# Displaying_Unit.net
KiCad netlist of a schematic drawn in Altium Designer
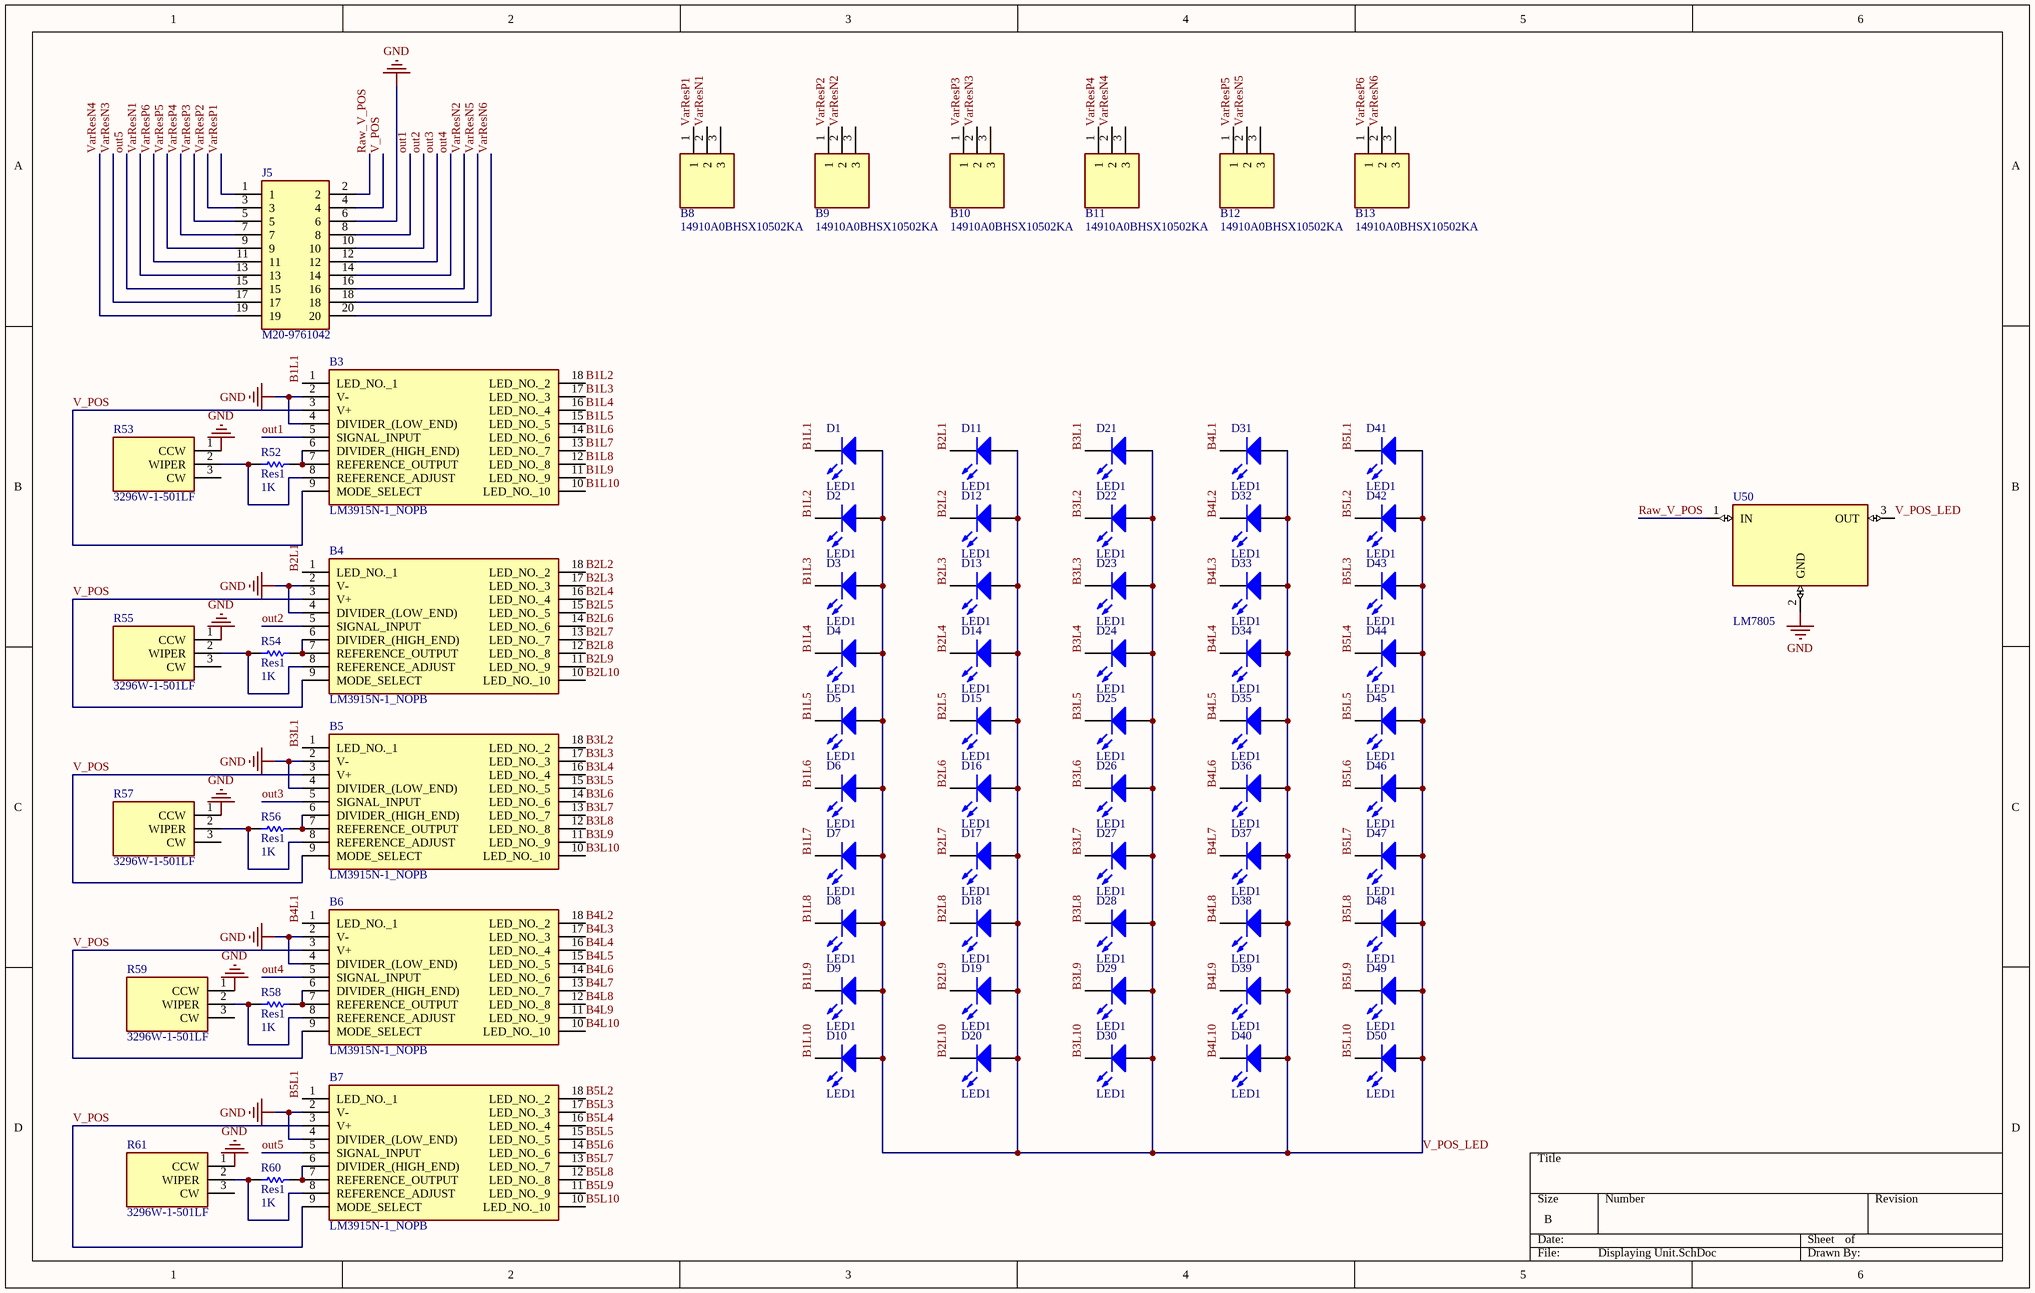
[diagram p0: Displaying Unit.SchDoc]

(export (version "E")
  (design (tool "Eeschema 10.0.6"))
  (components
    (comp (ref "B3")
      (value "LM3915N-1_NOPB")
      (footprint "DIP794W56P254L2286H533Q18N")
      (fields
        (field (name "MANUFACTURER_PART_NUMBER") "LM3915N-1/NOPB")
        (field (name "MOUSER PART NUMBER") "926-LM3915N-1/NOPB")
      )
      (libsource (lib "LM3915N-1_NOPB") (part "LM3915N-1_NOPB"))
    )
    (comp (ref "B4")
      (value "LM3915N-1_NOPB")
      (footprint "DIP794W56P254L2286H533Q18N")
      (fields
        (field (name "MANUFACTURER_PART_NUMBER") "LM3915N-1/NOPB")
        (field (name "MOUSER PART NUMBER") "926-LM3915N-1/NOPB")
      )
      (libsource (lib "LM3915N-1_NOPB") (part "LM3915N-1_NOPB"))
    )
    (comp (ref "B5")
      (value "LM3915N-1_NOPB")
      (footprint "DIP794W56P254L2286H533Q18N")
      (fields
        (field (name "MANUFACTURER_PART_NUMBER") "LM3915N-1/NOPB")
        (field (name "MOUSER PART NUMBER") "926-LM3915N-1/NOPB")
      )
      (libsource (lib "LM3915N-1_NOPB") (part "LM3915N-1_NOPB"))
    )
    (comp (ref "B6")
      (value "LM3915N-1_NOPB")
      (footprint "DIP794W56P254L2286H533Q18N")
      (fields
        (field (name "MANUFACTURER_PART_NUMBER") "LM3915N-1/NOPB")
        (field (name "MOUSER PART NUMBER") "926-LM3915N-1/NOPB")
      )
      (libsource (lib "LM3915N-1_NOPB") (part "LM3915N-1_NOPB"))
    )
    (comp (ref "B7")
      (value "LM3915N-1_NOPB")
      (footprint "DIP794W56P254L2286H533Q18N")
      (fields
        (field (name "MANUFACTURER_PART_NUMBER") "LM3915N-1/NOPB")
        (field (name "MOUSER PART NUMBER") "926-LM3915N-1/NOPB")
      )
      (libsource (lib "LM3915N-1_NOPB") (part "LM3915N-1_NOPB"))
    )
    (comp (ref "B8")
      (value "14910A0BHSX10502KA")
      (footprint "14910F0GJSX10103KA")
      (description "Potentiometers 1/2' SQ 1/4'S 5Kohms Cermet")
      (fields (field (name "MOUSER PART NUMBER") "594-14910A0BHSP502KA"))
      (libsource (lib "14910A0BHSX10502KA") (part "14910A0BHSX10502KA"))
    )
    (comp (ref "B9")
      (value "14910A0BHSX10502KA")
      (footprint "14910F0GJSX10103KA")
      (description "Potentiometers 1/2' SQ 1/4'S 5Kohms Cermet")
      (fields (field (name "MOUSER PART NUMBER") "594-14910A0BHSP502KA"))
      (libsource (lib "14910A0BHSX10502KA") (part "14910A0BHSX10502KA"))
    )
    (comp (ref "B10")
      (value "14910A0BHSX10502KA")
      (footprint "14910F0GJSX10103KA")
      (description "Potentiometers 1/2' SQ 1/4'S 5Kohms Cermet")
      (fields (field (name "MOUSER PART NUMBER") "594-14910A0BHSP502KA"))
      (libsource (lib "14910A0BHSX10502KA") (part "14910A0BHSX10502KA"))
    )
    (comp (ref "B11")
      (value "14910A0BHSX10502KA")
      (footprint "14910F0GJSX10103KA")
      (description "Potentiometers 1/2' SQ 1/4'S 5Kohms Cermet")
      (fields (field (name "MOUSER PART NUMBER") "594-14910A0BHSP502KA"))
      (libsource (lib "14910A0BHSX10502KA") (part "14910A0BHSX10502KA"))
    )
    (comp (ref "B12")
      (value "14910A0BHSX10502KA")
      (footprint "14910F0GJSX10103KA")
      (description "Potentiometers 1/2' SQ 1/4'S 5Kohms Cermet")
      (fields (field (name "MOUSER PART NUMBER") "594-14910A0BHSP502KA"))
      (libsource (lib "14910A0BHSX10502KA") (part "14910A0BHSX10502KA"))
    )
    (comp (ref "B13")
      (value "14910A0BHSX10502KA")
      (footprint "14910F0GJSX10103KA")
      (description "Potentiometers 1/2' SQ 1/4'S 5Kohms Cermet")
      (fields (field (name "MOUSER PART NUMBER") "594-14910A0BHSP502KA"))
      (libsource (lib "14910A0BHSX10502KA") (part "14910A0BHSX10502KA"))
    )
    (comp (ref "D1")
      (value "LED1")
      (footprint "LED-1")
      (description "Typical RED GaAs LED")
      (fields (field (name "PUBLISHER") "Altium Limited"))
      (libsource (lib "Miscellaneous Devices") (part "LED1"))
    )
    (comp (ref "D2")
      (value "LED1")
      (footprint "LED-1")
      (description "Typical RED GaAs LED")
      (fields (field (name "PUBLISHER") "Altium Limited"))
      (libsource (lib "Miscellaneous Devices") (part "LED1"))
    )
    (comp (ref "D3")
      (value "LED1")
      (footprint "LED-1")
      (description "Typical RED GaAs LED")
      (fields (field (name "PUBLISHER") "Altium Limited"))
      (libsource (lib "Miscellaneous Devices") (part "LED1"))
    )
    (comp (ref "D4")
      (value "LED1")
      (footprint "LED-1")
      (description "Typical RED GaAs LED")
      (fields (field (name "PUBLISHER") "Altium Limited"))
      (libsource (lib "Miscellaneous Devices") (part "LED1"))
    )
    (comp (ref "D5")
      (value "LED1")
      (footprint "LED-1")
      (description "Typical RED GaAs LED")
      (fields (field (name "PUBLISHER") "Altium Limited"))
      (libsource (lib "Miscellaneous Devices") (part "LED1"))
    )
    (comp (ref "D6")
      (value "LED1")
      (footprint "LED-1")
      (description "Typical RED GaAs LED")
      (fields (field (name "PUBLISHER") "Altium Limited"))
      (libsource (lib "Miscellaneous Devices") (part "LED1"))
    )
    (comp (ref "D7")
      (value "LED1")
      (footprint "LED-1")
      (description "Typical RED GaAs LED")
      (fields (field (name "PUBLISHER") "Altium Limited"))
      (libsource (lib "Miscellaneous Devices") (part "LED1"))
    )
    (comp (ref "D8")
      (value "LED1")
      (footprint "LED-1")
      (description "Typical RED GaAs LED")
      (fields (field (name "PUBLISHER") "Altium Limited"))
      (libsource (lib "Miscellaneous Devices") (part "LED1"))
    )
    (comp (ref "D9")
      (value "LED1")
      (footprint "LED-1")
      (description "Typical RED GaAs LED")
      (fields (field (name "PUBLISHER") "Altium Limited"))
      (libsource (lib "Miscellaneous Devices") (part "LED1"))
    )
    (comp (ref "D10")
      (value "LED1")
      (footprint "LED-1")
      (description "Typical RED GaAs LED")
      (fields (field (name "PUBLISHER") "Altium Limited"))
      (libsource (lib "Miscellaneous Devices") (part "LED1"))
    )
    (comp (ref "D11")
      (value "LED1")
      (footprint "LED-1")
      (description "Typical RED GaAs LED")
      (fields (field (name "PUBLISHER") "Altium Limited"))
      (libsource (lib "Miscellaneous Devices") (part "LED1"))
    )
    (comp (ref "D12")
      (value "LED1")
      (footprint "LED-1")
      (description "Typical RED GaAs LED")
      (fields (field (name "PUBLISHER") "Altium Limited"))
      (libsource (lib "Miscellaneous Devices") (part "LED1"))
    )
    (comp (ref "D13")
      (value "LED1")
      (footprint "LED-1")
      (description "Typical RED GaAs LED")
      (fields (field (name "PUBLISHER") "Altium Limited"))
      (libsource (lib "Miscellaneous Devices") (part "LED1"))
    )
    (comp (ref "D14")
      (value "LED1")
      (footprint "LED-1")
      (description "Typical RED GaAs LED")
      (fields (field (name "PUBLISHER") "Altium Limited"))
      (libsource (lib "Miscellaneous Devices") (part "LED1"))
    )
    (comp (ref "D15")
      (value "LED1")
      (footprint "LED-1")
      (description "Typical RED GaAs LED")
      (fields (field (name "PUBLISHER") "Altium Limited"))
      (libsource (lib "Miscellaneous Devices") (part "LED1"))
    )
    (comp (ref "D16")
      (value "LED1")
      (footprint "LED-1")
      (description "Typical RED GaAs LED")
      (fields (field (name "PUBLISHER") "Altium Limited"))
      (libsource (lib "Miscellaneous Devices") (part "LED1"))
    )
    (comp (ref "D17")
      (value "LED1")
      (footprint "LED-1")
      (description "Typical RED GaAs LED")
      (fields (field (name "PUBLISHER") "Altium Limited"))
      (libsource (lib "Miscellaneous Devices") (part "LED1"))
    )
    (comp (ref "D18")
      (value "LED1")
      (footprint "LED-1")
      (description "Typical RED GaAs LED")
      (fields (field (name "PUBLISHER") "Altium Limited"))
      (libsource (lib "Miscellaneous Devices") (part "LED1"))
    )
    (comp (ref "D19")
      (value "LED1")
      (footprint "LED-1")
      (description "Typical RED GaAs LED")
      (fields (field (name "PUBLISHER") "Altium Limited"))
      (libsource (lib "Miscellaneous Devices") (part "LED1"))
    )
    (comp (ref "D20")
      (value "LED1")
      (footprint "LED-1")
      (description "Typical RED GaAs LED")
      (fields (field (name "PUBLISHER") "Altium Limited"))
      (libsource (lib "Miscellaneous Devices") (part "LED1"))
    )
    (comp (ref "D21")
      (value "LED1")
      (footprint "LED-1")
      (description "Typical RED GaAs LED")
      (fields (field (name "PUBLISHER") "Altium Limited"))
      (libsource (lib "Miscellaneous Devices") (part "LED1"))
    )
    (comp (ref "D22")
      (value "LED1")
      (footprint "LED-1")
      (description "Typical RED GaAs LED")
      (fields (field (name "PUBLISHER") "Altium Limited"))
      (libsource (lib "Miscellaneous Devices") (part "LED1"))
    )
    (comp (ref "D23")
      (value "LED1")
      (footprint "LED-1")
      (description "Typical RED GaAs LED")
      (fields (field (name "PUBLISHER") "Altium Limited"))
      (libsource (lib "Miscellaneous Devices") (part "LED1"))
    )
    (comp (ref "D24")
      (value "LED1")
      (footprint "LED-1")
      (description "Typical RED GaAs LED")
      (fields (field (name "PUBLISHER") "Altium Limited"))
      (libsource (lib "Miscellaneous Devices") (part "LED1"))
    )
    (comp (ref "D25")
      (value "LED1")
      (footprint "LED-1")
      (description "Typical RED GaAs LED")
      (fields (field (name "PUBLISHER") "Altium Limited"))
      (libsource (lib "Miscellaneous Devices") (part "LED1"))
    )
    (comp (ref "D26")
      (value "LED1")
      (footprint "LED-1")
      (description "Typical RED GaAs LED")
      (fields (field (name "PUBLISHER") "Altium Limited"))
      (libsource (lib "Miscellaneous Devices") (part "LED1"))
    )
    (comp (ref "D27")
      (value "LED1")
      (footprint "LED-1")
      (description "Typical RED GaAs LED")
      (fields (field (name "PUBLISHER") "Altium Limited"))
      (libsource (lib "Miscellaneous Devices") (part "LED1"))
    )
    (comp (ref "D28")
      (value "LED1")
      (footprint "LED-1")
      (description "Typical RED GaAs LED")
      (fields (field (name "PUBLISHER") "Altium Limited"))
      (libsource (lib "Miscellaneous Devices") (part "LED1"))
    )
    (comp (ref "D29")
      (value "LED1")
      (footprint "LED-1")
      (description "Typical RED GaAs LED")
      (fields (field (name "PUBLISHER") "Altium Limited"))
      (libsource (lib "Miscellaneous Devices") (part "LED1"))
    )
    (comp (ref "D30")
      (value "LED1")
      (footprint "LED-1")
      (description "Typical RED GaAs LED")
      (fields (field (name "PUBLISHER") "Altium Limited"))
      (libsource (lib "Miscellaneous Devices") (part "LED1"))
    )
    (comp (ref "D31")
      (value "LED1")
      (footprint "LED-1")
      (description "Typical RED GaAs LED")
      (fields (field (name "PUBLISHER") "Altium Limited"))
      (libsource (lib "Miscellaneous Devices") (part "LED1"))
    )
    (comp (ref "D32")
      (value "LED1")
      (footprint "LED-1")
      (description "Typical RED GaAs LED")
      (fields (field (name "PUBLISHER") "Altium Limited"))
      (libsource (lib "Miscellaneous Devices") (part "LED1"))
    )
    (comp (ref "D33")
      (value "LED1")
      (footprint "LED-1")
      (description "Typical RED GaAs LED")
      (fields (field (name "PUBLISHER") "Altium Limited"))
      (libsource (lib "Miscellaneous Devices") (part "LED1"))
    )
    (comp (ref "D34")
      (value "LED1")
      (footprint "LED-1")
      (description "Typical RED GaAs LED")
      (fields (field (name "PUBLISHER") "Altium Limited"))
      (libsource (lib "Miscellaneous Devices") (part "LED1"))
    )
    (comp (ref "D35")
      (value "LED1")
      (footprint "LED-1")
      (description "Typical RED GaAs LED")
      (fields (field (name "PUBLISHER") "Altium Limited"))
      (libsource (lib "Miscellaneous Devices") (part "LED1"))
    )
    (comp (ref "D36")
      (value "LED1")
      (footprint "LED-1")
      (description "Typical RED GaAs LED")
      (fields (field (name "PUBLISHER") "Altium Limited"))
      (libsource (lib "Miscellaneous Devices") (part "LED1"))
    )
    (comp (ref "D37")
      (value "LED1")
      (footprint "LED-1")
      (description "Typical RED GaAs LED")
      (fields (field (name "PUBLISHER") "Altium Limited"))
      (libsource (lib "Miscellaneous Devices") (part "LED1"))
    )
    (comp (ref "D38")
      (value "LED1")
      (footprint "LED-1")
      (description "Typical RED GaAs LED")
      (fields (field (name "PUBLISHER") "Altium Limited"))
      (libsource (lib "Miscellaneous Devices") (part "LED1"))
    )
    (comp (ref "D39")
      (value "LED1")
      (footprint "LED-1")
      (description "Typical RED GaAs LED")
      (fields (field (name "PUBLISHER") "Altium Limited"))
      (libsource (lib "Miscellaneous Devices") (part "LED1"))
    )
    (comp (ref "D40")
      (value "LED1")
      (footprint "LED-1")
      (description "Typical RED GaAs LED")
      (fields (field (name "PUBLISHER") "Altium Limited"))
      (libsource (lib "Miscellaneous Devices") (part "LED1"))
    )
    (comp (ref "D41")
      (value "LED1")
      (footprint "LED-1")
      (description "Typical RED GaAs LED")
      (fields (field (name "PUBLISHER") "Altium Limited"))
      (libsource (lib "Miscellaneous Devices") (part "LED1"))
    )
    (comp (ref "D42")
      (value "LED1")
      (footprint "LED-1")
      (description "Typical RED GaAs LED")
      (fields (field (name "PUBLISHER") "Altium Limited"))
      (libsource (lib "Miscellaneous Devices") (part "LED1"))
    )
    (comp (ref "D43")
      (value "LED1")
      (footprint "LED-1")
      (description "Typical RED GaAs LED")
      (fields (field (name "PUBLISHER") "Altium Limited"))
      (libsource (lib "Miscellaneous Devices") (part "LED1"))
    )
    (comp (ref "D44")
      (value "LED1")
      (footprint "LED-1")
      (description "Typical RED GaAs LED")
      (fields (field (name "PUBLISHER") "Altium Limited"))
      (libsource (lib "Miscellaneous Devices") (part "LED1"))
    )
    (comp (ref "D45")
      (value "LED1")
      (footprint "LED-1")
      (description "Typical RED GaAs LED")
      (fields (field (name "PUBLISHER") "Altium Limited"))
      (libsource (lib "Miscellaneous Devices") (part "LED1"))
    )
    (comp (ref "D46")
      (value "LED1")
      (footprint "LED-1")
      (description "Typical RED GaAs LED")
      (fields (field (name "PUBLISHER") "Altium Limited"))
      (libsource (lib "Miscellaneous Devices") (part "LED1"))
    )
    (comp (ref "D47")
      (value "LED1")
      (footprint "LED-1")
      (description "Typical RED GaAs LED")
      (fields (field (name "PUBLISHER") "Altium Limited"))
      (libsource (lib "Miscellaneous Devices") (part "LED1"))
    )
    (comp (ref "D48")
      (value "LED1")
      (footprint "LED-1")
      (description "Typical RED GaAs LED")
      (fields (field (name "PUBLISHER") "Altium Limited"))
      (libsource (lib "Miscellaneous Devices") (part "LED1"))
    )
    (comp (ref "D49")
      (value "LED1")
      (footprint "LED-1")
      (description "Typical RED GaAs LED")
      (fields (field (name "PUBLISHER") "Altium Limited"))
      (libsource (lib "Miscellaneous Devices") (part "LED1"))
    )
    (comp (ref "D50")
      (value "LED1")
      (footprint "LED-1")
      (description "Typical RED GaAs LED")
      (fields (field (name "PUBLISHER") "Altium Limited"))
      (libsource (lib "Miscellaneous Devices") (part "LED1"))
    )
    (comp (ref "J5")
      (value "M20-9761042")
      (footprint "HDRV20W64P254_2X10_2540X508X838P")
      (description "Headers & Wire Housings 10+10 DIL VERTICAL PIN HEADER GOLD+TIN")
      (fields (field (name "MOUSER PART NUMBER") "855-M20-9761042"))
      (libsource (lib "M20-9761042") (part "M20-9761042"))
    )
    (comp (ref "R52")
      (value "Res1")
      (footprint "AXIAL-0.3")
      (description "Resistor")
      (fields (field (name "ALTIUM_VALUE") "1K") (field (name "PUBLISHER") "Altium Limited"))
      (libsource (lib "Miscellaneous Devices") (part "Res1"))
    )
    (comp (ref "R53")
      (value "3296W-1-501LF")
      (footprint "3296W1501LF")
      (description "Trimmer Resistors - Through Hole 3/8IN 500 OHM Sealed Vertical Adjust")
      (fields (field (name "MOUSER PART NUMBER") "652-3296W-1-501LF"))
      (libsource (lib "3296W-1-501LF") (part "3296W-1-501LF"))
    )
    (comp (ref "R54")
      (value "Res1")
      (footprint "AXIAL-0.3")
      (description "Resistor")
      (fields (field (name "ALTIUM_VALUE") "1K") (field (name "PUBLISHER") "Altium Limited"))
      (libsource (lib "Miscellaneous Devices") (part "Res1"))
    )
    (comp (ref "R55")
      (value "3296W-1-501LF")
      (footprint "3296W1501LF")
      (description "Trimmer Resistors - Through Hole 3/8IN 500 OHM Sealed Vertical Adjust")
      (fields (field (name "MOUSER PART NUMBER") "652-3296W-1-501LF"))
      (libsource (lib "3296W-1-501LF") (part "3296W-1-501LF"))
    )
    (comp (ref "R56")
      (value "Res1")
      (footprint "AXIAL-0.3")
      (description "Resistor")
      (fields (field (name "ALTIUM_VALUE") "1K") (field (name "PUBLISHER") "Altium Limited"))
      (libsource (lib "Miscellaneous Devices") (part "Res1"))
    )
    (comp (ref "R57")
      (value "3296W-1-501LF")
      (footprint "3296W1501LF")
      (description "Trimmer Resistors - Through Hole 3/8IN 500 OHM Sealed Vertical Adjust")
      (fields (field (name "MOUSER PART NUMBER") "652-3296W-1-501LF"))
      (libsource (lib "3296W-1-501LF") (part "3296W-1-501LF"))
    )
    (comp (ref "R58")
      (value "Res1")
      (footprint "AXIAL-0.3")
      (description "Resistor")
      (fields (field (name "ALTIUM_VALUE") "1K") (field (name "PUBLISHER") "Altium Limited"))
      (libsource (lib "Miscellaneous Devices") (part "Res1"))
    )
    (comp (ref "R59")
      (value "3296W-1-501LF")
      (footprint "3296W1501LF")
      (description "Trimmer Resistors - Through Hole 3/8IN 500 OHM Sealed Vertical Adjust")
      (fields (field (name "MOUSER PART NUMBER") "652-3296W-1-501LF"))
      (libsource (lib "3296W-1-501LF") (part "3296W-1-501LF"))
    )
    (comp (ref "R60")
      (value "Res1")
      (footprint "AXIAL-0.3")
      (description "Resistor")
      (fields (field (name "ALTIUM_VALUE") "1K") (field (name "PUBLISHER") "Altium Limited"))
      (libsource (lib "Miscellaneous Devices") (part "Res1"))
    )
    (comp (ref "R61")
      (value "3296W-1-501LF")
      (footprint "3296W1501LF")
      (description "Trimmer Resistors - Through Hole 3/8IN 500 OHM Sealed Vertical Adjust")
      (fields (field (name "MOUSER PART NUMBER") "652-3296W-1-501LF"))
      (libsource (lib "3296W-1-501LF") (part "3296W-1-501LF"))
    )
    (comp (ref "U50")
      (value "LM7805")
      (footprint "TO220")
      (description "Linear Voltage Regulator IC Positive Fixed 1 Output 1.5A DDPAK/TO-263-3")
      (fields (field (name "MF") "Texas Instruments"))
      (libsource (lib "LM7805") (part "LM7805"))
    )
  )
  (nets
    (net (code "1") (name "/B1L1") (class "Default")
      (node (ref "B3") (pin "1") (pinfunction "LED_NO._1_1") (pintype "passive"))
      (node (ref "D1") (pin "2") (pinfunction "K_2") (pintype "passive"))
    )
    (net (code "2") (name "/B1L2") (class "Default")
      (node (ref "B3") (pin "18") (pinfunction "LED_NO._2_18") (pintype "passive"))
      (node (ref "D2") (pin "2") (pinfunction "K_2") (pintype "passive"))
    )
    (net (code "3") (name "/B1L3") (class "Default")
      (node (ref "B3") (pin "17") (pinfunction "LED_NO._3_17") (pintype "passive"))
      (node (ref "D3") (pin "2") (pinfunction "K_2") (pintype "passive"))
    )
    (net (code "4") (name "/B1L4") (class "Default")
      (node (ref "B3") (pin "16") (pinfunction "LED_NO._4_16") (pintype "passive"))
      (node (ref "D4") (pin "2") (pinfunction "K_2") (pintype "passive"))
    )
    (net (code "5") (name "/B1L5") (class "Default")
      (node (ref "B3") (pin "15") (pinfunction "LED_NO._5_15") (pintype "passive"))
      (node (ref "D5") (pin "2") (pinfunction "K_2") (pintype "passive"))
    )
    (net (code "6") (name "/B1L6") (class "Default")
      (node (ref "B3") (pin "14") (pinfunction "LED_NO._6_14") (pintype "passive"))
      (node (ref "D6") (pin "2") (pinfunction "K_2") (pintype "passive"))
    )
    (net (code "7") (name "/B1L7") (class "Default")
      (node (ref "B3") (pin "13") (pinfunction "LED_NO._7_13") (pintype "passive"))
      (node (ref "D7") (pin "2") (pinfunction "K_2") (pintype "passive"))
    )
    (net (code "8") (name "/B1L8") (class "Default")
      (node (ref "B3") (pin "12") (pinfunction "LED_NO._8_12") (pintype "passive"))
      (node (ref "D8") (pin "2") (pinfunction "K_2") (pintype "passive"))
    )
    (net (code "9") (name "/B1L9") (class "Default")
      (node (ref "B3") (pin "11") (pinfunction "LED_NO._9_11") (pintype "passive"))
      (node (ref "D9") (pin "2") (pinfunction "K_2") (pintype "passive"))
    )
    (net (code "10") (name "/B1L10") (class "Default")
      (node (ref "B3") (pin "10") (pinfunction "LED_NO._10_10") (pintype "passive"))
      (node (ref "D10") (pin "2") (pinfunction "K_2") (pintype "passive"))
    )
    (net (code "11") (name "/B2L1") (class "Default")
      (node (ref "B4") (pin "1") (pinfunction "LED_NO._1_1") (pintype "passive"))
      (node (ref "D11") (pin "2") (pinfunction "K_2") (pintype "passive"))
    )
    (net (code "12") (name "/B2L2") (class "Default")
      (node (ref "B4") (pin "18") (pinfunction "LED_NO._2_18") (pintype "passive"))
      (node (ref "D12") (pin "2") (pinfunction "K_2") (pintype "passive"))
    )
    (net (code "13") (name "/B2L3") (class "Default")
      (node (ref "B4") (pin "17") (pinfunction "LED_NO._3_17") (pintype "passive"))
      (node (ref "D13") (pin "2") (pinfunction "K_2") (pintype "passive"))
    )
    (net (code "14") (name "/B2L4") (class "Default")
      (node (ref "B4") (pin "16") (pinfunction "LED_NO._4_16") (pintype "passive"))
      (node (ref "D14") (pin "2") (pinfunction "K_2") (pintype "passive"))
    )
    (net (code "15") (name "/B2L5") (class "Default")
      (node (ref "B4") (pin "15") (pinfunction "LED_NO._5_15") (pintype "passive"))
      (node (ref "D15") (pin "2") (pinfunction "K_2") (pintype "passive"))
    )
    (net (code "16") (name "/B2L6") (class "Default")
      (node (ref "B4") (pin "14") (pinfunction "LED_NO._6_14") (pintype "passive"))
      (node (ref "D16") (pin "2") (pinfunction "K_2") (pintype "passive"))
    )
    (net (code "17") (name "/B2L7") (class "Default")
      (node (ref "B4") (pin "13") (pinfunction "LED_NO._7_13") (pintype "passive"))
      (node (ref "D17") (pin "2") (pinfunction "K_2") (pintype "passive"))
    )
    (net (code "18") (name "/B2L8") (class "Default")
      (node (ref "B4") (pin "12") (pinfunction "LED_NO._8_12") (pintype "passive"))
      (node (ref "D18") (pin "2") (pinfunction "K_2") (pintype "passive"))
    )
    (net (code "19") (name "/B2L9") (class "Default")
      (node (ref "B4") (pin "11") (pinfunction "LED_NO._9_11") (pintype "passive"))
      (node (ref "D19") (pin "2") (pinfunction "K_2") (pintype "passive"))
    )
    (net (code "20") (name "/B2L10") (class "Default")
      (node (ref "B4") (pin "10") (pinfunction "LED_NO._10_10") (pintype "passive"))
      (node (ref "D20") (pin "2") (pinfunction "K_2") (pintype "passive"))
    )
    (net (code "21") (name "/B3L1") (class "Default")
      (node (ref "B5") (pin "1") (pinfunction "LED_NO._1_1") (pintype "passive"))
      (node (ref "D21") (pin "2") (pinfunction "K_2") (pintype "passive"))
    )
    (net (code "22") (name "/B3L2") (class "Default")
      (node (ref "B5") (pin "18") (pinfunction "LED_NO._2_18") (pintype "passive"))
      (node (ref "D22") (pin "2") (pinfunction "K_2") (pintype "passive"))
    )
    (net (code "23") (name "/B3L3") (class "Default")
      (node (ref "B5") (pin "17") (pinfunction "LED_NO._3_17") (pintype "passive"))
      (node (ref "D23") (pin "2") (pinfunction "K_2") (pintype "passive"))
    )
    (net (code "24") (name "/B3L4") (class "Default")
      (node (ref "B5") (pin "16") (pinfunction "LED_NO._4_16") (pintype "passive"))
      (node (ref "D24") (pin "2") (pinfunction "K_2") (pintype "passive"))
    )
    (net (code "25") (name "/B3L5") (class "Default")
      (node (ref "B5") (pin "15") (pinfunction "LED_NO._5_15") (pintype "passive"))
      (node (ref "D25") (pin "2") (pinfunction "K_2") (pintype "passive"))
    )
    (net (code "26") (name "/B3L6") (class "Default")
      (node (ref "B5") (pin "14") (pinfunction "LED_NO._6_14") (pintype "passive"))
      (node (ref "D26") (pin "2") (pinfunction "K_2") (pintype "passive"))
    )
    (net (code "27") (name "/B3L7") (class "Default")
      (node (ref "B5") (pin "13") (pinfunction "LED_NO._7_13") (pintype "passive"))
      (node (ref "D27") (pin "2") (pinfunction "K_2") (pintype "passive"))
    )
    (net (code "28") (name "/B3L8") (class "Default")
      (node (ref "B5") (pin "12") (pinfunction "LED_NO._8_12") (pintype "passive"))
      (node (ref "D28") (pin "2") (pinfunction "K_2") (pintype "passive"))
    )
    (net (code "29") (name "/B3L9") (class "Default")
      (node (ref "B5") (pin "11") (pinfunction "LED_NO._9_11") (pintype "passive"))
      (node (ref "D29") (pin "2") (pinfunction "K_2") (pintype "passive"))
    )
    (net (code "30") (name "/B3L10") (class "Default")
      (node (ref "B5") (pin "10") (pinfunction "LED_NO._10_10") (pintype "passive"))
      (node (ref "D30") (pin "2") (pinfunction "K_2") (pintype "passive"))
    )
    (net (code "31") (name "/B4L1") (class "Default")
      (node (ref "B6") (pin "1") (pinfunction "LED_NO._1_1") (pintype "passive"))
      (node (ref "D31") (pin "2") (pinfunction "K_2") (pintype "passive"))
    )
    (net (code "32") (name "/B4L2") (class "Default")
      (node (ref "B6") (pin "18") (pinfunction "LED_NO._2_18") (pintype "passive"))
      (node (ref "D32") (pin "2") (pinfunction "K_2") (pintype "passive"))
    )
    (net (code "33") (name "/B4L3") (class "Default")
      (node (ref "B6") (pin "17") (pinfunction "LED_NO._3_17") (pintype "passive"))
      (node (ref "D33") (pin "2") (pinfunction "K_2") (pintype "passive"))
    )
    (net (code "34") (name "/B4L4") (class "Default")
      (node (ref "B6") (pin "16") (pinfunction "LED_NO._4_16") (pintype "passive"))
      (node (ref "D34") (pin "2") (pinfunction "K_2") (pintype "passive"))
    )
    (net (code "35") (name "/B4L5") (class "Default")
      (node (ref "B6") (pin "15") (pinfunction "LED_NO._5_15") (pintype "passive"))
      (node (ref "D35") (pin "2") (pinfunction "K_2") (pintype "passive"))
    )
    (net (code "36") (name "/B4L6") (class "Default")
      (node (ref "B6") (pin "14") (pinfunction "LED_NO._6_14") (pintype "passive"))
      (node (ref "D36") (pin "2") (pinfunction "K_2") (pintype "passive"))
    )
    (net (code "37") (name "/B4L7") (class "Default")
      (node (ref "B6") (pin "13") (pinfunction "LED_NO._7_13") (pintype "passive"))
      (node (ref "D37") (pin "2") (pinfunction "K_2") (pintype "passive"))
    )
    (net (code "38") (name "/B4L8") (class "Default")
      (node (ref "B6") (pin "12") (pinfunction "LED_NO._8_12") (pintype "passive"))
      (node (ref "D38") (pin "2") (pinfunction "K_2") (pintype "passive"))
    )
    (net (code "39") (name "/B4L9") (class "Default")
      (node (ref "B6") (pin "11") (pinfunction "LED_NO._9_11") (pintype "passive"))
      (node (ref "D39") (pin "2") (pinfunction "K_2") (pintype "passive"))
    )
    (net (code "40") (name "/B4L10") (class "Default")
      (node (ref "B6") (pin "10") (pinfunction "LED_NO._10_10") (pintype "passive"))
      (node (ref "D40") (pin "2") (pinfunction "K_2") (pintype "passive"))
    )
    (net (code "41") (name "/B5L1") (class "Default")
      (node (ref "B7") (pin "1") (pinfunction "LED_NO._1_1") (pintype "passive"))
      (node (ref "D41") (pin "2") (pinfunction "K_2") (pintype "passive"))
    )
    (net (code "42") (name "/B5L2") (class "Default")
      (node (ref "B7") (pin "18") (pinfunction "LED_NO._2_18") (pintype "passive"))
      (node (ref "D42") (pin "2") (pinfunction "K_2") (pintype "passive"))
    )
    (net (code "43") (name "/B5L3") (class "Default")
      (node (ref "B7") (pin "17") (pinfunction "LED_NO._3_17") (pintype "passive"))
      (node (ref "D43") (pin "2") (pinfunction "K_2") (pintype "passive"))
    )
    (net (code "44") (name "/B5L4") (class "Default")
      (node (ref "B7") (pin "16") (pinfunction "LED_NO._4_16") (pintype "passive"))
      (node (ref "D44") (pin "2") (pinfunction "K_2") (pintype "passive"))
    )
    (net (code "45") (name "/B5L5") (class "Default")
      (node (ref "B7") (pin "15") (pinfunction "LED_NO._5_15") (pintype "passive"))
      (node (ref "D45") (pin "2") (pinfunction "K_2") (pintype "passive"))
    )
    (net (code "46") (name "/B5L6") (class "Default")
      (node (ref "B7") (pin "14") (pinfunction "LED_NO._6_14") (pintype "passive"))
      (node (ref "D46") (pin "2") (pinfunction "K_2") (pintype "passive"))
    )
    (net (code "47") (name "/B5L7") (class "Default")
      (node (ref "B7") (pin "13") (pinfunction "LED_NO._7_13") (pintype "passive"))
      (node (ref "D47") (pin "2") (pinfunction "K_2") (pintype "passive"))
    )
    (net (code "48") (name "/B5L8") (class "Default")
      (node (ref "B7") (pin "12") (pinfunction "LED_NO._8_12") (pintype "passive"))
      (node (ref "D48") (pin "2") (pinfunction "K_2") (pintype "passive"))
    )
    (net (code "49") (name "/B5L9") (class "Default")
      (node (ref "B7") (pin "11") (pinfunction "LED_NO._9_11") (pintype "passive"))
      (node (ref "D49") (pin "2") (pinfunction "K_2") (pintype "passive"))
    )
    (net (code "50") (name "/B5L10") (class "Default")
      (node (ref "B7") (pin "10") (pinfunction "LED_NO._10_10") (pintype "passive"))
      (node (ref "D50") (pin "2") (pinfunction "K_2") (pintype "passive"))
    )
    (net (code "51") (name "/Raw_V_POS") (class "Default")
      (node (ref "J5") (pin "2") (pinfunction "2_2") (pintype "passive"))
      (node (ref "U50") (pin "1") (pinfunction "IN_1") (pintype "bidirectional"))
    )
    (net (code "52") (name "/V_POS") (class "Default")
      (node (ref "B3") (pin "3") (pinfunction "V+_3") (pintype "passive"))
      (node (ref "B3") (pin "9") (pinfunction "MODE_SELECT_9") (pintype "passive"))
      (node (ref "B4") (pin "3") (pinfunction "V+_3") (pintype "passive"))
      (node (ref "B4") (pin "9") (pinfunction "MODE_SELECT_9") (pintype "passive"))
      (node (ref "B5") (pin "3") (pinfunction "V+_3") (pintype "passive"))
      (node (ref "B5") (pin "9") (pinfunction "MODE_SELECT_9") (pintype "passive"))
      (node (ref "B6") (pin "3") (pinfunction "V+_3") (pintype "passive"))
      (node (ref "B6") (pin "9") (pinfunction "MODE_SELECT_9") (pintype "passive"))
      (node (ref "B7") (pin "3") (pinfunction "V+_3") (pintype "passive"))
      (node (ref "B7") (pin "9") (pinfunction "MODE_SELECT_9") (pintype "passive"))
      (node (ref "J5") (pin "4") (pinfunction "4_4") (pintype "passive"))
    )
    (net (code "53") (name "/V_POS_LED") (class "Default")
      (node (ref "D1") (pin "1") (pinfunction "A_1") (pintype "passive"))
      (node (ref "D10") (pin "1") (pinfunction "A_1") (pintype "passive"))
      (node (ref "D11") (pin "1") (pinfunction "A_1") (pintype "passive"))
      (node (ref "D12") (pin "1") (pinfunction "A_1") (pintype "passive"))
      (node (ref "D13") (pin "1") (pinfunction "A_1") (pintype "passive"))
      (node (ref "D14") (pin "1") (pinfunction "A_1") (pintype "passive"))
      (node (ref "D15") (pin "1") (pinfunction "A_1") (pintype "passive"))
      (node (ref "D16") (pin "1") (pinfunction "A_1") (pintype "passive"))
      (node (ref "D17") (pin "1") (pinfunction "A_1") (pintype "passive"))
      (node (ref "D18") (pin "1") (pinfunction "A_1") (pintype "passive"))
      (node (ref "D19") (pin "1") (pinfunction "A_1") (pintype "passive"))
      (node (ref "D2") (pin "1") (pinfunction "A_1") (pintype "passive"))
      (node (ref "D20") (pin "1") (pinfunction "A_1") (pintype "passive"))
      (node (ref "D21") (pin "1") (pinfunction "A_1") (pintype "passive"))
      (node (ref "D22") (pin "1") (pinfunction "A_1") (pintype "passive"))
      (node (ref "D23") (pin "1") (pinfunction "A_1") (pintype "passive"))
      (node (ref "D24") (pin "1") (pinfunction "A_1") (pintype "passive"))
      (node (ref "D25") (pin "1") (pinfunction "A_1") (pintype "passive"))
      (node (ref "D26") (pin "1") (pinfunction "A_1") (pintype "passive"))
      (node (ref "D27") (pin "1") (pinfunction "A_1") (pintype "passive"))
      (node (ref "D28") (pin "1") (pinfunction "A_1") (pintype "passive"))
      (node (ref "D29") (pin "1") (pinfunction "A_1") (pintype "passive"))
      (node (ref "D3") (pin "1") (pinfunction "A_1") (pintype "passive"))
      (node (ref "D30") (pin "1") (pinfunction "A_1") (pintype "passive"))
      (node (ref "D31") (pin "1") (pinfunction "A_1") (pintype "passive"))
      (node (ref "D32") (pin "1") (pinfunction "A_1") (pintype "passive"))
      (node (ref "D33") (pin "1") (pinfunction "A_1") (pintype "passive"))
      (node (ref "D34") (pin "1") (pinfunction "A_1") (pintype "passive"))
      (node (ref "D35") (pin "1") (pinfunction "A_1") (pintype "passive"))
      (node (ref "D36") (pin "1") (pinfunction "A_1") (pintype "passive"))
      (node (ref "D37") (pin "1") (pinfunction "A_1") (pintype "passive"))
      (node (ref "D38") (pin "1") (pinfunction "A_1") (pintype "passive"))
      (node (ref "D39") (pin "1") (pinfunction "A_1") (pintype "passive"))
      (node (ref "D4") (pin "1") (pinfunction "A_1") (pintype "passive"))
      (node (ref "D40") (pin "1") (pinfunction "A_1") (pintype "passive"))
      (node (ref "D41") (pin "1") (pinfunction "A_1") (pintype "passive"))
      (node (ref "D42") (pin "1") (pinfunction "A_1") (pintype "passive"))
      (node (ref "D43") (pin "1") (pinfunction "A_1") (pintype "passive"))
      (node (ref "D44") (pin "1") (pinfunction "A_1") (pintype "passive"))
      (node (ref "D45") (pin "1") (pinfunction "A_1") (pintype "passive"))
      (node (ref "D46") (pin "1") (pinfunction "A_1") (pintype "passive"))
      (node (ref "D47") (pin "1") (pinfunction "A_1") (pintype "passive"))
      (node (ref "D48") (pin "1") (pinfunction "A_1") (pintype "passive"))
      (node (ref "D49") (pin "1") (pinfunction "A_1") (pintype "passive"))
      (node (ref "D5") (pin "1") (pinfunction "A_1") (pintype "passive"))
      (node (ref "D50") (pin "1") (pinfunction "A_1") (pintype "passive"))
      (node (ref "D6") (pin "1") (pinfunction "A_1") (pintype "passive"))
      (node (ref "D7") (pin "1") (pinfunction "A_1") (pintype "passive"))
      (node (ref "D8") (pin "1") (pinfunction "A_1") (pintype "passive"))
      (node (ref "D9") (pin "1") (pinfunction "A_1") (pintype "passive"))
      (node (ref "U50") (pin "3") (pinfunction "OUT_3") (pintype "bidirectional"))
    )
    (net (code "54") (name "/VarResN1") (class "Default")
      (node (ref "B8") (pin "2") (pinfunction "2_2") (pintype "passive"))
      (node (ref "J5") (pin "13") (pinfunction "13_13") (pintype "passive"))
    )
    (net (code "55") (name "/VarResN2") (class "Default")
      (node (ref "B9") (pin "2") (pinfunction "2_2") (pintype "passive"))
      (node (ref "J5") (pin "16") (pinfunction "16_16") (pintype "passive"))
    )
    (net (code "56") (name "/VarResN3") (class "Default")
      (node (ref "B10") (pin "2") (pinfunction "2_2") (pintype "passive"))
      (node (ref "J5") (pin "17") (pinfunction "17_17") (pintype "passive"))
    )
    (net (code "57") (name "/VarResN4") (class "Default")
      (node (ref "B11") (pin "2") (pinfunction "2_2") (pintype "passive"))
      (node (ref "J5") (pin "19") (pinfunction "19_19") (pintype "passive"))
    )
    (net (code "58") (name "/VarResN5") (class "Default")
      (node (ref "B12") (pin "2") (pinfunction "2_2") (pintype "passive"))
      (node (ref "J5") (pin "18") (pinfunction "18_18") (pintype "passive"))
    )
    (net (code "59") (name "/VarResN6") (class "Default")
      (node (ref "B13") (pin "2") (pinfunction "2_2") (pintype "passive"))
      (node (ref "J5") (pin "20") (pinfunction "20_20") (pintype "passive"))
    )
    (net (code "60") (name "/VarResP1") (class "Default")
      (node (ref "B8") (pin "1") (pinfunction "1_1") (pintype "passive"))
      (node (ref "J5") (pin "1") (pinfunction "1_1") (pintype "passive"))
    )
    (net (code "61") (name "/VarResP2") (class "Default")
      (node (ref "B9") (pin "1") (pinfunction "1_1") (pintype "passive"))
      (node (ref "J5") (pin "3") (pinfunction "3_3") (pintype "passive"))
    )
    (net (code "62") (name "/VarResP3") (class "Default")
      (node (ref "B10") (pin "1") (pinfunction "1_1") (pintype "passive"))
      (node (ref "J5") (pin "5") (pinfunction "5_5") (pintype "passive"))
    )
    (net (code "63") (name "/VarResP4") (class "Default")
      (node (ref "B11") (pin "1") (pinfunction "1_1") (pintype "passive"))
      (node (ref "J5") (pin "7") (pinfunction "7_7") (pintype "passive"))
    )
    (net (code "64") (name "/VarResP5") (class "Default")
      (node (ref "B12") (pin "1") (pinfunction "1_1") (pintype "passive"))
      (node (ref "J5") (pin "9") (pinfunction "9_9") (pintype "passive"))
    )
    (net (code "65") (name "/VarResP6") (class "Default")
      (node (ref "B13") (pin "1") (pinfunction "1_1") (pintype "passive"))
      (node (ref "J5") (pin "11") (pinfunction "11_11") (pintype "passive"))
    )
    (net (code "66") (name "/out1") (class "Default")
      (node (ref "B3") (pin "5") (pinfunction "SIGNAL_INPUT_5") (pintype "passive"))
      (node (ref "J5") (pin "8") (pinfunction "8_8") (pintype "passive"))
    )
    (net (code "67") (name "/out2") (class "Default")
      (node (ref "B4") (pin "5") (pinfunction "SIGNAL_INPUT_5") (pintype "passive"))
      (node (ref "J5") (pin "10") (pinfunction "10_10") (pintype "passive"))
    )
    (net (code "68") (name "/out3") (class "Default")
      (node (ref "B5") (pin "5") (pinfunction "SIGNAL_INPUT_5") (pintype "passive"))
      (node (ref "J5") (pin "12") (pinfunction "12_12") (pintype "passive"))
    )
    (net (code "69") (name "/out4") (class "Default")
      (node (ref "B6") (pin "5") (pinfunction "SIGNAL_INPUT_5") (pintype "passive"))
      (node (ref "J5") (pin "14") (pinfunction "14_14") (pintype "passive"))
    )
    (net (code "70") (name "/out5") (class "Default")
      (node (ref "B7") (pin "5") (pinfunction "SIGNAL_INPUT_5") (pintype "passive"))
      (node (ref "J5") (pin "15") (pinfunction "15_15") (pintype "passive"))
    )
    (net (code "71") (name "GND") (class "Default")
      (node (ref "B3") (pin "2") (pinfunction "V-_2") (pintype "passive"))
      (node (ref "B3") (pin "4") (pinfunction "DIVIDER_(LOW_END)_4") (pintype "passive"))
      (node (ref "B4") (pin "2") (pinfunction "V-_2") (pintype "passive"))
      (node (ref "B4") (pin "4") (pinfunction "DIVIDER_(LOW_END)_4") (pintype "passive"))
      (node (ref "B5") (pin "2") (pinfunction "V-_2") (pintype "passive"))
      (node (ref "B5") (pin "4") (pinfunction "DIVIDER_(LOW_END)_4") (pintype "passive"))
      (node (ref "B6") (pin "2") (pinfunction "V-_2") (pintype "passive"))
      (node (ref "B6") (pin "4") (pinfunction "DIVIDER_(LOW_END)_4") (pintype "passive"))
      (node (ref "B7") (pin "2") (pinfunction "V-_2") (pintype "passive"))
      (node (ref "B7") (pin "4") (pinfunction "DIVIDER_(LOW_END)_4") (pintype "passive"))
      (node (ref "J5") (pin "6") (pinfunction "6_6") (pintype "passive"))
      (node (ref "R53") (pin "1") (pinfunction "CCW_1") (pintype "passive"))
      (node (ref "R55") (pin "1") (pinfunction "CCW_1") (pintype "passive"))
      (node (ref "R57") (pin "1") (pinfunction "CCW_1") (pintype "passive"))
      (node (ref "R59") (pin "1") (pinfunction "CCW_1") (pintype "passive"))
      (node (ref "R61") (pin "1") (pinfunction "CCW_1") (pintype "passive"))
      (node (ref "U50") (pin "2") (pinfunction "GND_2") (pintype "bidirectional"))
    )
    (net (code "72") (name "Net-(B3-DIVIDER_(HIGH_END))") (class "Default")
      (node (ref "B3") (pin "6") (pinfunction "DIVIDER_(HIGH_END)_6") (pintype "passive"))
      (node (ref "B3") (pin "7") (pinfunction "REFERENCE_OUTPUT_7") (pintype "passive"))
      (node (ref "R52") (pin "2") (pinfunction "2_2") (pintype "passive"))
    )
    (net (code "73") (name "Net-(B3-REFERENCE_ADJUST)") (class "Default")
      (node (ref "B3") (pin "8") (pinfunction "REFERENCE_ADJUST_8") (pintype "passive"))
      (node (ref "R52") (pin "1") (pinfunction "1_1") (pintype "passive"))
      (node (ref "R53") (pin "2") (pinfunction "WIPER_2") (pintype "passive"))
    )
    (net (code "74") (name "Net-(B4-DIVIDER_(HIGH_END))") (class "Default")
      (node (ref "B4") (pin "6") (pinfunction "DIVIDER_(HIGH_END)_6") (pintype "passive"))
      (node (ref "B4") (pin "7") (pinfunction "REFERENCE_OUTPUT_7") (pintype "passive"))
      (node (ref "R54") (pin "2") (pinfunction "2_2") (pintype "passive"))
    )
    (net (code "75") (name "Net-(B4-REFERENCE_ADJUST)") (class "Default")
      (node (ref "B4") (pin "8") (pinfunction "REFERENCE_ADJUST_8") (pintype "passive"))
      (node (ref "R54") (pin "1") (pinfunction "1_1") (pintype "passive"))
      (node (ref "R55") (pin "2") (pinfunction "WIPER_2") (pintype "passive"))
    )
    (net (code "76") (name "Net-(B5-DIVIDER_(HIGH_END))") (class "Default")
      (node (ref "B5") (pin "6") (pinfunction "DIVIDER_(HIGH_END)_6") (pintype "passive"))
      (node (ref "B5") (pin "7") (pinfunction "REFERENCE_OUTPUT_7") (pintype "passive"))
      (node (ref "R56") (pin "2") (pinfunction "2_2") (pintype "passive"))
    )
    (net (code "77") (name "Net-(B5-REFERENCE_ADJUST)") (class "Default")
      (node (ref "B5") (pin "8") (pinfunction "REFERENCE_ADJUST_8") (pintype "passive"))
      (node (ref "R56") (pin "1") (pinfunction "1_1") (pintype "passive"))
      (node (ref "R57") (pin "2") (pinfunction "WIPER_2") (pintype "passive"))
    )
    (net (code "78") (name "Net-(B6-DIVIDER_(HIGH_END))") (class "Default")
      (node (ref "B6") (pin "6") (pinfunction "DIVIDER_(HIGH_END)_6") (pintype "passive"))
      (node (ref "B6") (pin "7") (pinfunction "REFERENCE_OUTPUT_7") (pintype "passive"))
      (node (ref "R58") (pin "2") (pinfunction "2_2") (pintype "passive"))
    )
    (net (code "79") (name "Net-(B6-REFERENCE_ADJUST)") (class "Default")
      (node (ref "B6") (pin "8") (pinfunction "REFERENCE_ADJUST_8") (pintype "passive"))
      (node (ref "R58") (pin "1") (pinfunction "1_1") (pintype "passive"))
      (node (ref "R59") (pin "2") (pinfunction "WIPER_2") (pintype "passive"))
    )
    (net (code "80") (name "Net-(B7-DIVIDER_(HIGH_END))") (class "Default")
      (node (ref "B7") (pin "6") (pinfunction "DIVIDER_(HIGH_END)_6") (pintype "passive"))
      (node (ref "B7") (pin "7") (pinfunction "REFERENCE_OUTPUT_7") (pintype "passive"))
      (node (ref "R60") (pin "2") (pinfunction "2_2") (pintype "passive"))
    )
    (net (code "81") (name "Net-(B7-REFERENCE_ADJUST)") (class "Default")
      (node (ref "B7") (pin "8") (pinfunction "REFERENCE_ADJUST_8") (pintype "passive"))
      (node (ref "R60") (pin "1") (pinfunction "1_1") (pintype "passive"))
      (node (ref "R61") (pin "2") (pinfunction "WIPER_2") (pintype "passive"))
    )
    (net (code "82") (name "unconnected-(B8-Pad3)") (class "Default")
      (node (ref "B8") (pin "3") (pinfunction "3_3") (pintype "passive"))
    )
    (net (code "83") (name "unconnected-(B9-Pad3)") (class "Default")
      (node (ref "B9") (pin "3") (pinfunction "3_3") (pintype "passive"))
    )
    (net (code "84") (name "unconnected-(B10-Pad3)") (class "Default")
      (node (ref "B10") (pin "3") (pinfunction "3_3") (pintype "passive"))
    )
    (net (code "85") (name "unconnected-(B11-Pad3)") (class "Default")
      (node (ref "B11") (pin "3") (pinfunction "3_3") (pintype "passive"))
    )
    (net (code "86") (name "unconnected-(B12-Pad3)") (class "Default")
      (node (ref "B12") (pin "3") (pinfunction "3_3") (pintype "passive"))
    )
    (net (code "87") (name "unconnected-(B13-Pad3)") (class "Default")
      (node (ref "B13") (pin "3") (pinfunction "3_3") (pintype "passive"))
    )
    (net (code "88") (name "unconnected-(R53-CW-Pad3)") (class "Default")
      (node (ref "R53") (pin "3") (pinfunction "CW_3") (pintype "passive"))
    )
    (net (code "89") (name "unconnected-(R55-CW-Pad3)") (class "Default")
      (node (ref "R55") (pin "3") (pinfunction "CW_3") (pintype "passive"))
    )
    (net (code "90") (name "unconnected-(R57-CW-Pad3)") (class "Default")
      (node (ref "R57") (pin "3") (pinfunction "CW_3") (pintype "passive"))
    )
    (net (code "91") (name "unconnected-(R59-CW-Pad3)") (class "Default")
      (node (ref "R59") (pin "3") (pinfunction "CW_3") (pintype "passive"))
    )
    (net (code "92") (name "unconnected-(R61-CW-Pad3)") (class "Default")
      (node (ref "R61") (pin "3") (pinfunction "CW_3") (pintype "passive"))
    )
  )
)
